# uCurrentRev5.net
KiCad netlist of a schematic drawn in Altium Designer
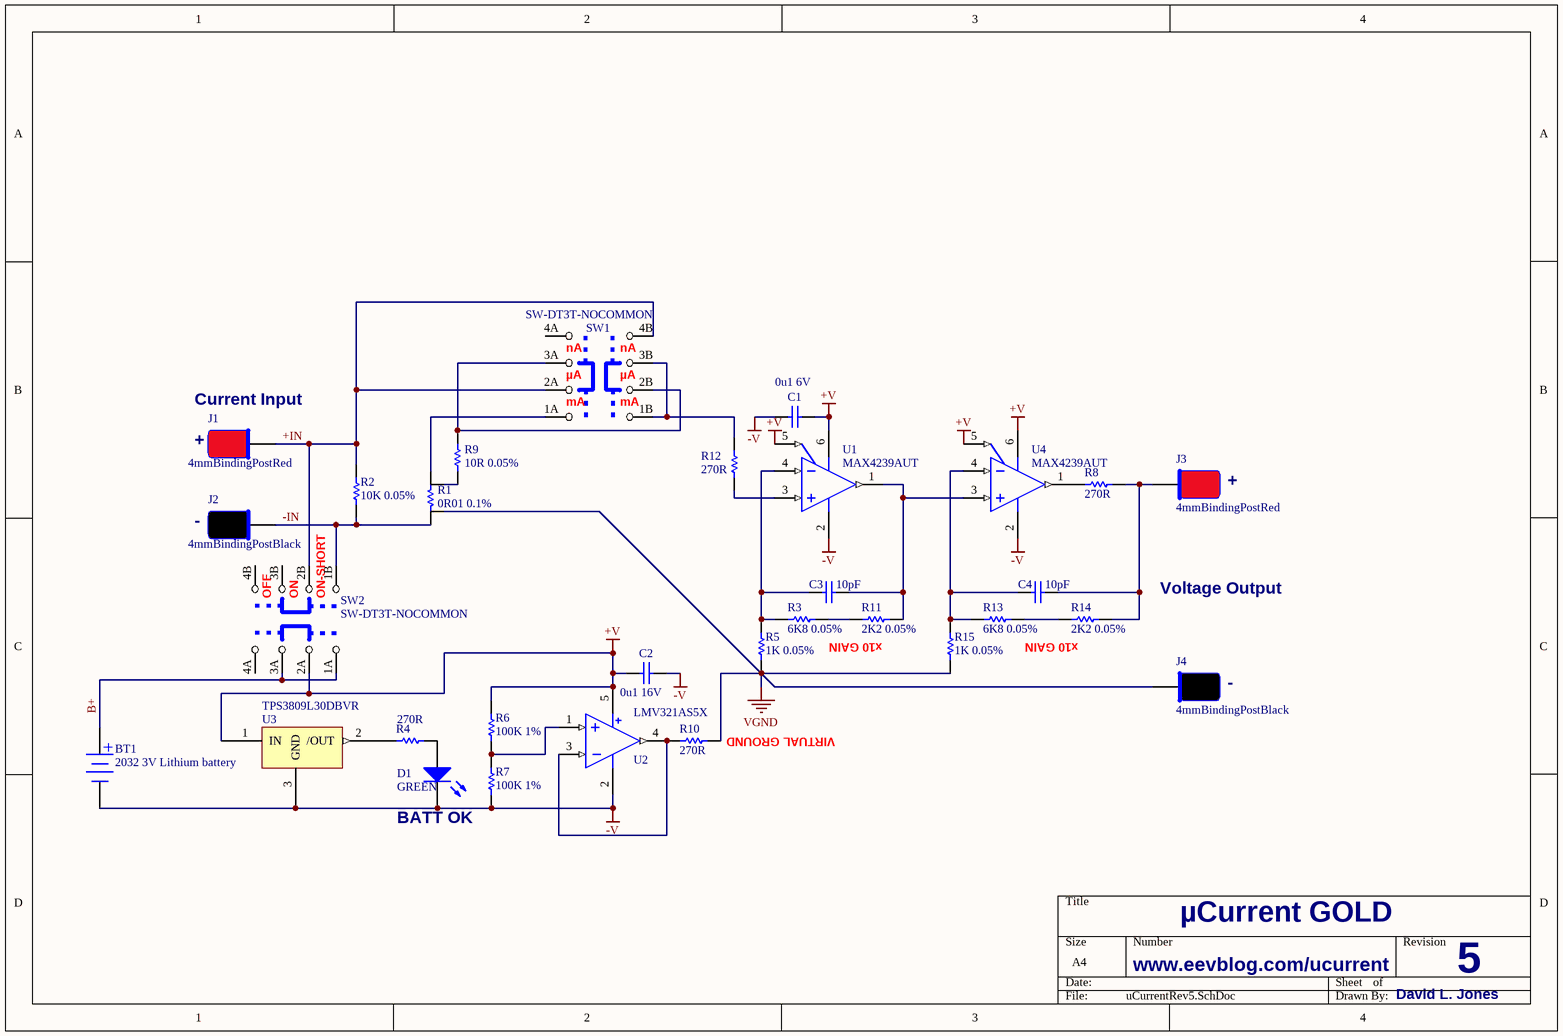
[diagram p0: uCurrentRev5.SchDoc]

(export (version "E")
  (design (tool "Eeschema 10.0.6"))
  (components
    (comp (ref "BT1")
      (value "2032 3V Lithium battery")
      (footprint "2032 SMD Holder")
      (description "Lithium Battery Holder for CR2032 3V Cell")
      (libsource (lib "AltiumDesignLibrary") (part "CON-CELLBATT"))
    )
    (comp (ref "C1")
      (value "0u1 6V")
      (footprint "CAPC1608N")
      (description "Capacitor, Ceramic, 4.7uF 10% 16V 0805 (2012) X7R")
      (fields (field (name "TOLERANCE") "10 %"))
      (libsource (lib "AltiumDesignLibrary") (part "CAP-NP"))
    )
    (comp (ref "C2")
      (value "0u1 16V")
      (footprint "CAPC1608N")
      (description "Capacitor, Ceramic, 4.7uF 10% 16V 0805 (2012) X7R")
      (fields (field (name "TOLERANCE") "10 %"))
      (libsource (lib "AltiumDesignLibrary") (part "CAP-NP"))
    )
    (comp (ref "C3")
      (value "10pF")
      (footprint "CAPC1608N")
      (description "Capacitor, Ceramic, 4.7uF 10% 16V 0805 (2012) X7R")
      (fields (field (name "TOLERANCE") "10 %"))
      (libsource (lib "AltiumDesignLibrary") (part "CAP-NP"))
    )
    (comp (ref "C4")
      (value "10pF")
      (footprint "CAPC1608N")
      (description "Capacitor, Ceramic, 4.7uF 10% 16V 0805 (2012) X7R")
      (fields (field (name "TOLERANCE") "10 %"))
      (libsource (lib "AltiumDesignLibrary") (part "CAP-NP"))
    )
    (comp (ref "D1")
      (value "GREEN")
      (footprint "1206reverseLED")
      (description "LED, Red 0805 (2012) HSMH-C170")
      (libsource (lib "AltiumDesignLibrary") (part "DIO-LED-1S"))
    )
    (comp (ref "J1")
      (value "4mmBindingPostRed")
      (footprint "4mmBindingPost")
      (libsource (lib "EEVblog") (part "4mmBindingPostRed"))
    )
    (comp (ref "J2")
      (value "4mmBindingPostBlack")
      (footprint "4mmBindingPost")
      (libsource (lib "EEVblog") (part "4mmBindingPostBlack"))
    )
    (comp (ref "J3")
      (value "4mmBindingPostRed")
      (footprint "4mmBindingPost")
      (libsource (lib "EEVblog") (part "4mmBindingPostRed"))
    )
    (comp (ref "J4")
      (value "4mmBindingPostBlack")
      (footprint "4mmBindingPost")
      (libsource (lib "EEVblog") (part "4mmBindingPostBlack"))
    )
    (comp (ref "R1")
      (value "0R01 0.1%")
      (footprint "2512shuntresistor")
      (description "1206 current shunt")
      (libsource (lib "uCurrent") (part "1206currentShunt"))
    )
    (comp (ref "R2")
      (value "10K 0.05%")
      (footprint "RESC1608N")
      (description "Resistor, 75R 1% 0805 (2012)")
      (fields (field (name "TOLERANCE") "1 %"))
      (libsource (lib "AltiumDesignLibrary") (part "RES"))
    )
    (comp (ref "R3")
      (value "6K8 0.05%")
      (footprint "RESC1608N")
      (description "Resistor, 75R 1% 0805 (2012)")
      (fields (field (name "TOLERANCE") "1 %"))
      (libsource (lib "AltiumDesignLibrary") (part "RES"))
    )
    (comp (ref "R4")
      (value "270R")
      (footprint "RESC1608N")
      (description "Resistor, 75R 1% 0805 (2012)")
      (fields (field (name "TOLERANCE") "1 %"))
      (libsource (lib "AltiumDesignLibrary") (part "RES"))
    )
    (comp (ref "R5")
      (value "1K 0.05%")
      (footprint "RESC1608N")
      (description "Resistor, 75R 1% 0805 (2012)")
      (fields (field (name "TOLERANCE") "1 %"))
      (libsource (lib "AltiumDesignLibrary") (part "RES"))
    )
    (comp (ref "R6")
      (value "100K 1%")
      (footprint "RESC1608N")
      (description "Resistor, 75R 1% 0805 (2012)")
      (fields (field (name "TOLERANCE") "1 %"))
      (libsource (lib "AltiumDesignLibrary") (part "RES"))
    )
    (comp (ref "R7")
      (value "100K 1%")
      (footprint "RESC1608N")
      (description "Resistor, 75R 1% 0805 (2012)")
      (fields (field (name "TOLERANCE") "1 %"))
      (libsource (lib "AltiumDesignLibrary") (part "RES"))
    )
    (comp (ref "R8")
      (value "270R")
      (footprint "RESC1608N")
      (description "Resistor, 75R 1% 0805 (2012)")
      (fields (field (name "TOLERANCE") "1 %"))
      (libsource (lib "AltiumDesignLibrary") (part "RES"))
    )
    (comp (ref "R9")
      (value "10R 0.05%")
      (footprint "RESC2012N")
      (description "Resistor, 75R 1% 0805 (2012)")
      (fields (field (name "TOLERANCE") "1 %"))
      (libsource (lib "AltiumDesignLibrary") (part "RES"))
    )
    (comp (ref "R10")
      (value "270R")
      (footprint "RESC1608N")
      (description "Resistor, 75R 1% 0805 (2012)")
      (fields (field (name "TOLERANCE") "1 %"))
      (libsource (lib "AltiumDesignLibrary") (part "RES"))
    )
    (comp (ref "R11")
      (value "2K2 0.05%")
      (footprint "RESC1608N")
      (description "Resistor, 75R 1% 0805 (2012)")
      (fields (field (name "TOLERANCE") "1 %"))
      (libsource (lib "AltiumDesignLibrary") (part "RES"))
    )
    (comp (ref "R12")
      (value "270R")
      (footprint "RESC1608N")
      (description "Resistor, 75R 1% 0805 (2012)")
      (fields (field (name "TOLERANCE") "1 %"))
      (libsource (lib "AltiumDesignLibrary") (part "RES"))
    )
    (comp (ref "R13")
      (value "6K8 0.05%")
      (footprint "RESC1608N")
      (description "Resistor, 75R 1% 0805 (2012)")
      (fields (field (name "TOLERANCE") "1 %"))
      (libsource (lib "AltiumDesignLibrary") (part "RES"))
    )
    (comp (ref "R14")
      (value "2K2 0.05%")
      (footprint "RESC1608N")
      (description "Resistor, 75R 1% 0805 (2012)")
      (fields (field (name "TOLERANCE") "1 %"))
      (libsource (lib "AltiumDesignLibrary") (part "RES"))
    )
    (comp (ref "R15")
      (value "1K 0.05%")
      (footprint "RESC1608N")
      (description "Resistor, 75R 1% 0805 (2012)")
      (fields (field (name "TOLERANCE") "1 %"))
      (libsource (lib "AltiumDesignLibrary") (part "RES"))
    )
    (comp (ref "SW1")
      (value "SW-DT3T-NOCOMMON")
      (footprint "SW_L203011MS02")
      (libsource (lib "EEVblog") (part "SW-DT3T-NOCOMMON"))
    )
    (comp (ref "SW2")
      (value "SW-DT3T-NOCOMMON")
      (footprint "SW_L203011MS02")
      (libsource (lib "EEVblog") (part "SW-DT3T-NOCOMMON"))
    )
    (comp (ref "U1")
      (value "MAX4239AUT")
      (footprint "SOT-23-CH6_N")
      (fields (field (name "PUBLISHER") "Altium Limited"))
      (libsource (lib "Microchip Linear Devices") (part "MCP6273T-E/CH"))
    )
    (comp (ref "U2")
      (value "LMV321AS5X")
      (footprint "SOT23-5AL")
      (description "2.7V GP Opamp")
      (fields (field (name "PUBLISHER") "Altium Limited"))
      (libsource (lib "uCurrent") (part "LMV321"))
    )
    (comp (ref "U3")
      (value "TPS3809L30DBVR")
      (footprint "SOT23")
      (libsource (lib "uCurrent") (part "VoltageSupervisor"))
    )
    (comp (ref "U4")
      (value "MAX4239AUT")
      (footprint "SOT-23-CH6_N")
      (fields (field (name "PUBLISHER") "Altium Limited"))
      (libsource (lib "Microchip Linear Devices") (part "MCP6273T-E/CH"))
    )
  )
  (nets
    (net (code "1") (name "+V") (class "Default")
      (node (ref "C1") (pin "2") (pinfunction "2_2") (pintype "passive"))
      (node (ref "C2") (pin "1") (pinfunction "1_1") (pintype "passive"))
      (node (ref "R6") (pin "2") (pinfunction "2_2") (pintype "passive"))
      (node (ref "SW2") (pin "2A") (pinfunction "2A_2A") (pintype "passive"))
      (node (ref "U1") (pin "5") (pinfunction "~{CS}_5") (pintype "input"))
      (node (ref "U1") (pin "6") (pinfunction "VDD_6") (pintype "power_in"))
      (node (ref "U2") (pin "5") (pinfunction "V+_5") (pintype "power_in"))
      (node (ref "U3") (pin "1") (pinfunction "IN_1") (pintype "power_in"))
      (node (ref "U4") (pin "5") (pinfunction "~{CS}_5") (pintype "input"))
      (node (ref "U4") (pin "6") (pinfunction "VDD_6") (pintype "power_in"))
    )
    (net (code "2") (name "-V") (class "Default")
      (node (ref "BT1") (pin "2") (pinfunction "-_2") (pintype "passive"))
      (node (ref "C1") (pin "1") (pinfunction "1_1") (pintype "passive"))
      (node (ref "C2") (pin "2") (pinfunction "2_2") (pintype "passive"))
      (node (ref "D1") (pin "2") (pinfunction "K_2") (pintype "passive"))
      (node (ref "R7") (pin "2") (pinfunction "2_2") (pintype "passive"))
      (node (ref "U1") (pin "2") (pinfunction "VSS_2") (pintype "power_in"))
      (node (ref "U2") (pin "2") (pinfunction "2_2") (pintype "power_in"))
      (node (ref "U3") (pin "3") (pinfunction "GND_3") (pintype "power_in"))
      (node (ref "U4") (pin "2") (pinfunction "VSS_2") (pintype "power_in"))
    )
    (net (code "3") (name "/+IN") (class "Default")
      (node (ref "J1") (pin "1") (pinfunction "NOISE_1") (pintype "passive"))
      (node (ref "R2") (pin "1") (pinfunction "1_1") (pintype "passive"))
      (node (ref "SW1") (pin "2A") (pinfunction "2A_2A") (pintype "passive"))
      (node (ref "SW1") (pin "4B") (pinfunction "4B_4B") (pintype "passive"))
      (node (ref "SW2") (pin "2B") (pinfunction "2A_2B") (pintype "passive"))
    )
    (net (code "4") (name "/-IN") (class "Default")
      (node (ref "J2") (pin "1") (pinfunction "NOISE_1") (pintype "passive"))
      (node (ref "R1") (pin "2") (pinfunction "2_2") (pintype "passive"))
      (node (ref "R2") (pin "2") (pinfunction "2_2") (pintype "passive"))
      (node (ref "SW2") (pin "1B") (pinfunction "1B_1B") (pintype "passive"))
    )
    (net (code "5") (name "/B+") (class "Default")
      (node (ref "BT1") (pin "1") (pinfunction "+_1") (pintype "passive"))
      (node (ref "SW2") (pin "1A") (pinfunction "1A_1A") (pintype "passive"))
      (node (ref "SW2") (pin "3A") (pinfunction "3A_3A") (pintype "passive"))
    )
    (net (code "6") (name "Net-(D1-A)") (class "Default")
      (node (ref "D1") (pin "1") (pinfunction "A_1") (pintype "passive"))
      (node (ref "R4") (pin "1") (pinfunction "1_1") (pintype "passive"))
    )
    (net (code "7") (name "Net-(J3-NOISE)") (class "Default")
      (node (ref "C4") (pin "2") (pinfunction "2_2") (pintype "passive"))
      (node (ref "J3") (pin "1") (pinfunction "NOISE_1") (pintype "passive"))
      (node (ref "R14") (pin "2") (pinfunction "2_2") (pintype "passive"))
      (node (ref "R8") (pin "1") (pinfunction "1_1") (pintype "passive"))
    )
    (net (code "8") (name "Net-(R1-Pad1)") (class "Default")
      (node (ref "R1") (pin "1") (pinfunction "1_1") (pintype "passive"))
      (node (ref "SW1") (pin "1A") (pinfunction "1A_1A") (pintype "passive"))
    )
    (net (code "9") (name "Net-(R1-Pad3)") (class "Default")
      (node (ref "R1") (pin "3") (pinfunction "3_3") (pintype "passive"))
      (node (ref "R9") (pin "2") (pinfunction "2_2") (pintype "passive"))
    )
    (net (code "10") (name "Net-(R9-Pad1)") (class "Default")
      (node (ref "R9") (pin "1") (pinfunction "1_1") (pintype "passive"))
      (node (ref "SW1") (pin "2B") (pinfunction "2A_2B") (pintype "passive"))
      (node (ref "SW1") (pin "3A") (pinfunction "3A_3A") (pintype "passive"))
    )
    (net (code "11") (name "Net-(R11-Pad1)") (class "Default")
      (node (ref "R11") (pin "1") (pinfunction "1_1") (pintype "passive"))
      (node (ref "R3") (pin "2") (pinfunction "2_2") (pintype "passive"))
    )
    (net (code "12") (name "Net-(R12-Pad1)") (class "Default")
      (node (ref "R12") (pin "1") (pinfunction "1_1") (pintype "passive"))
      (node (ref "SW1") (pin "1B") (pinfunction "1B_1B") (pintype "passive"))
      (node (ref "SW1") (pin "3B") (pinfunction "3B_3B") (pintype "passive"))
    )
    (net (code "13") (name "Net-(R13-Pad2)") (class "Default")
      (node (ref "R13") (pin "2") (pinfunction "2_2") (pintype "passive"))
      (node (ref "R14") (pin "1") (pinfunction "1_1") (pintype "passive"))
    )
    (net (code "14") (name "Net-(U1-VIN+)") (class "Default")
      (node (ref "R12") (pin "2") (pinfunction "2_2") (pintype "passive"))
      (node (ref "U1") (pin "3") (pinfunction "VIN+_3") (pintype "input"))
    )
    (net (code "15") (name "Net-(U1-VIN-)") (class "Default")
      (node (ref "C3") (pin "1") (pinfunction "1_1") (pintype "passive"))
      (node (ref "R3") (pin "1") (pinfunction "1_1") (pintype "passive"))
      (node (ref "R5") (pin "1") (pinfunction "1_1") (pintype "passive"))
      (node (ref "U1") (pin "4") (pinfunction "VIN-_4") (pintype "input"))
    )
    (net (code "16") (name "Net-(U1-VOUT)") (class "Default")
      (node (ref "C3") (pin "2") (pinfunction "2_2") (pintype "passive"))
      (node (ref "R11") (pin "2") (pinfunction "2_2") (pintype "passive"))
      (node (ref "U1") (pin "1") (pinfunction "VOUT_1") (pintype "output"))
      (node (ref "U4") (pin "3") (pinfunction "VIN+_3") (pintype "input"))
    )
    (net (code "17") (name "Net-(U2-IN+)") (class "Default")
      (node (ref "R6") (pin "1") (pinfunction "1_1") (pintype "passive"))
      (node (ref "R7") (pin "1") (pinfunction "1_1") (pintype "passive"))
      (node (ref "U2") (pin "1") (pinfunction "IN+_1") (pintype "input"))
    )
    (net (code "18") (name "Net-(U2-IN-)") (class "Default")
      (node (ref "R10") (pin "2") (pinfunction "2_2") (pintype "passive"))
      (node (ref "U2") (pin "3") (pinfunction "IN-_3") (pintype "input"))
      (node (ref "U2") (pin "4") (pinfunction "OUT_4") (pintype "output"))
    )
    (net (code "19") (name "Net-(U3-{slash}OUT)") (class "Default")
      (node (ref "R4") (pin "2") (pinfunction "2_2") (pintype "passive"))
      (node (ref "U3") (pin "2") (pinfunction "/OUT_2") (pintype "output"))
    )
    (net (code "20") (name "Net-(U4-VIN-)") (class "Default")
      (node (ref "C4") (pin "1") (pinfunction "1_1") (pintype "passive"))
      (node (ref "R13") (pin "1") (pinfunction "1_1") (pintype "passive"))
      (node (ref "R15") (pin "1") (pinfunction "1_1") (pintype "passive"))
      (node (ref "U4") (pin "4") (pinfunction "VIN-_4") (pintype "input"))
    )
    (net (code "21") (name "Net-(U4-VOUT)") (class "Default")
      (node (ref "R8") (pin "2") (pinfunction "2_2") (pintype "passive"))
      (node (ref "U4") (pin "1") (pinfunction "VOUT_1") (pintype "output"))
    )
    (net (code "22") (name "VGND") (class "Default")
      (node (ref "J4") (pin "1") (pinfunction "NOISE_1") (pintype "passive"))
      (node (ref "R1") (pin "4") (pinfunction "4_4") (pintype "passive"))
      (node (ref "R10") (pin "1") (pinfunction "1_1") (pintype "passive"))
      (node (ref "R15") (pin "2") (pinfunction "2_2") (pintype "passive"))
      (node (ref "R5") (pin "2") (pinfunction "2_2") (pintype "passive"))
    )
    (net (code "23") (name "unconnected-(SW1-Pad4A)") (class "Default")
      (node (ref "SW1") (pin "4A") (pinfunction "4A_4A") (pintype "passive"))
    )
    (net (code "24") (name "unconnected-(SW2-Pad3B)") (class "Default")
      (node (ref "SW2") (pin "3B") (pinfunction "3B_3B") (pintype "passive"))
    )
    (net (code "25") (name "unconnected-(SW2-Pad4A)") (class "Default")
      (node (ref "SW2") (pin "4A") (pinfunction "4A_4A") (pintype "passive"))
    )
    (net (code "26") (name "unconnected-(SW2-Pad4B)") (class "Default")
      (node (ref "SW2") (pin "4B") (pinfunction "4B_4B") (pintype "passive"))
    )
  )
)
